# PreContV1.net
KiCad netlist of a schematic drawn in EAGLE
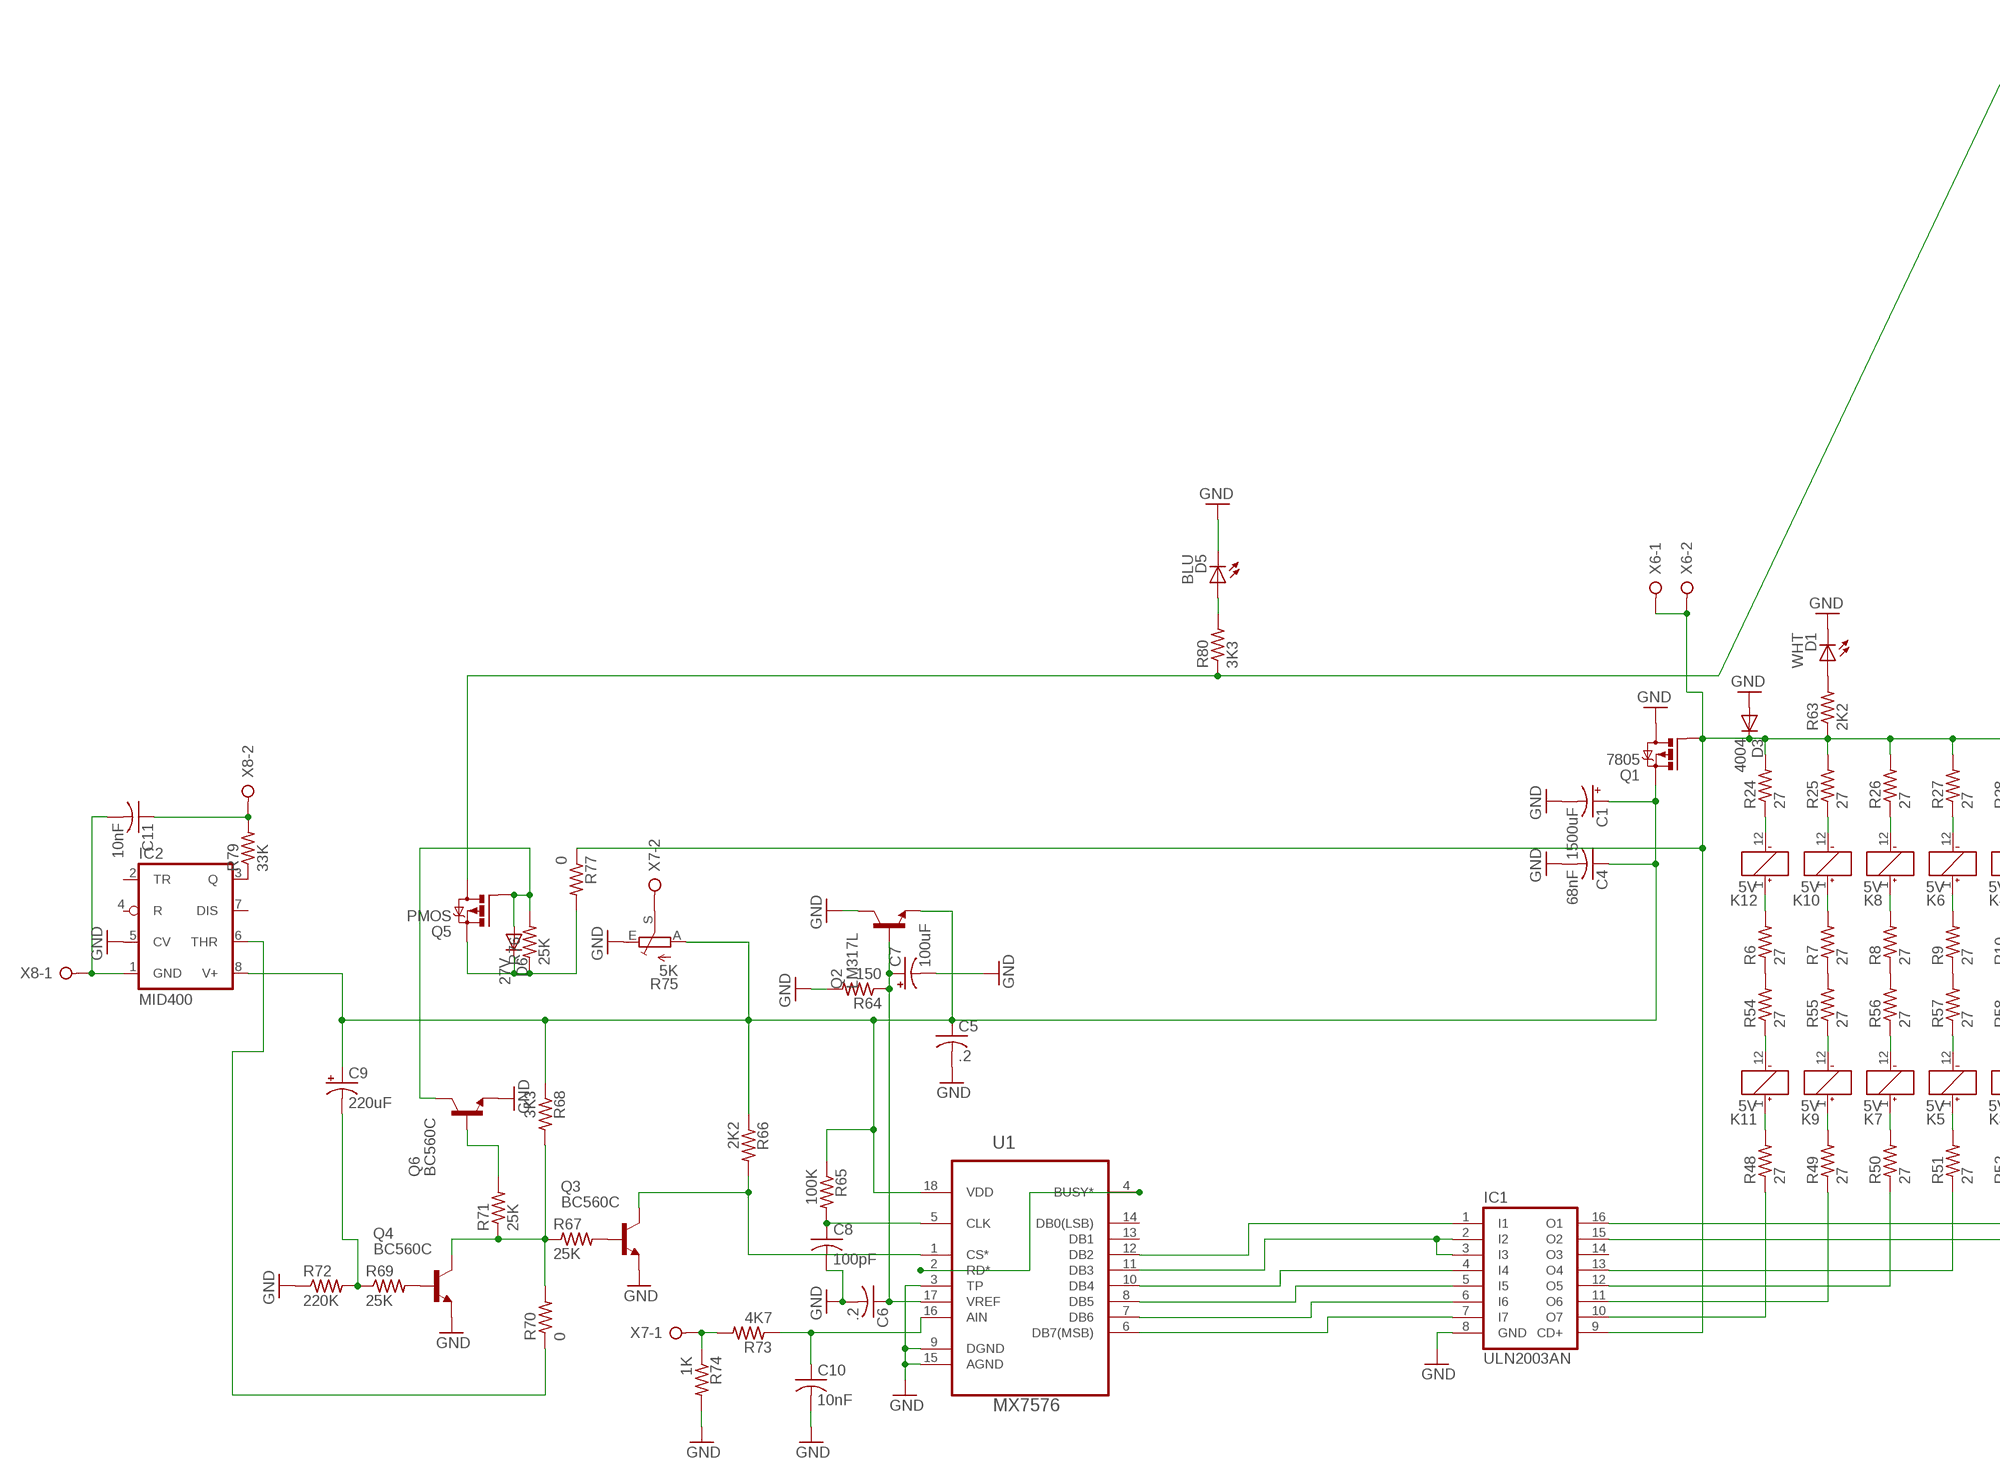
[diagram p0: schematic, sheet 1, part 1 of 2]
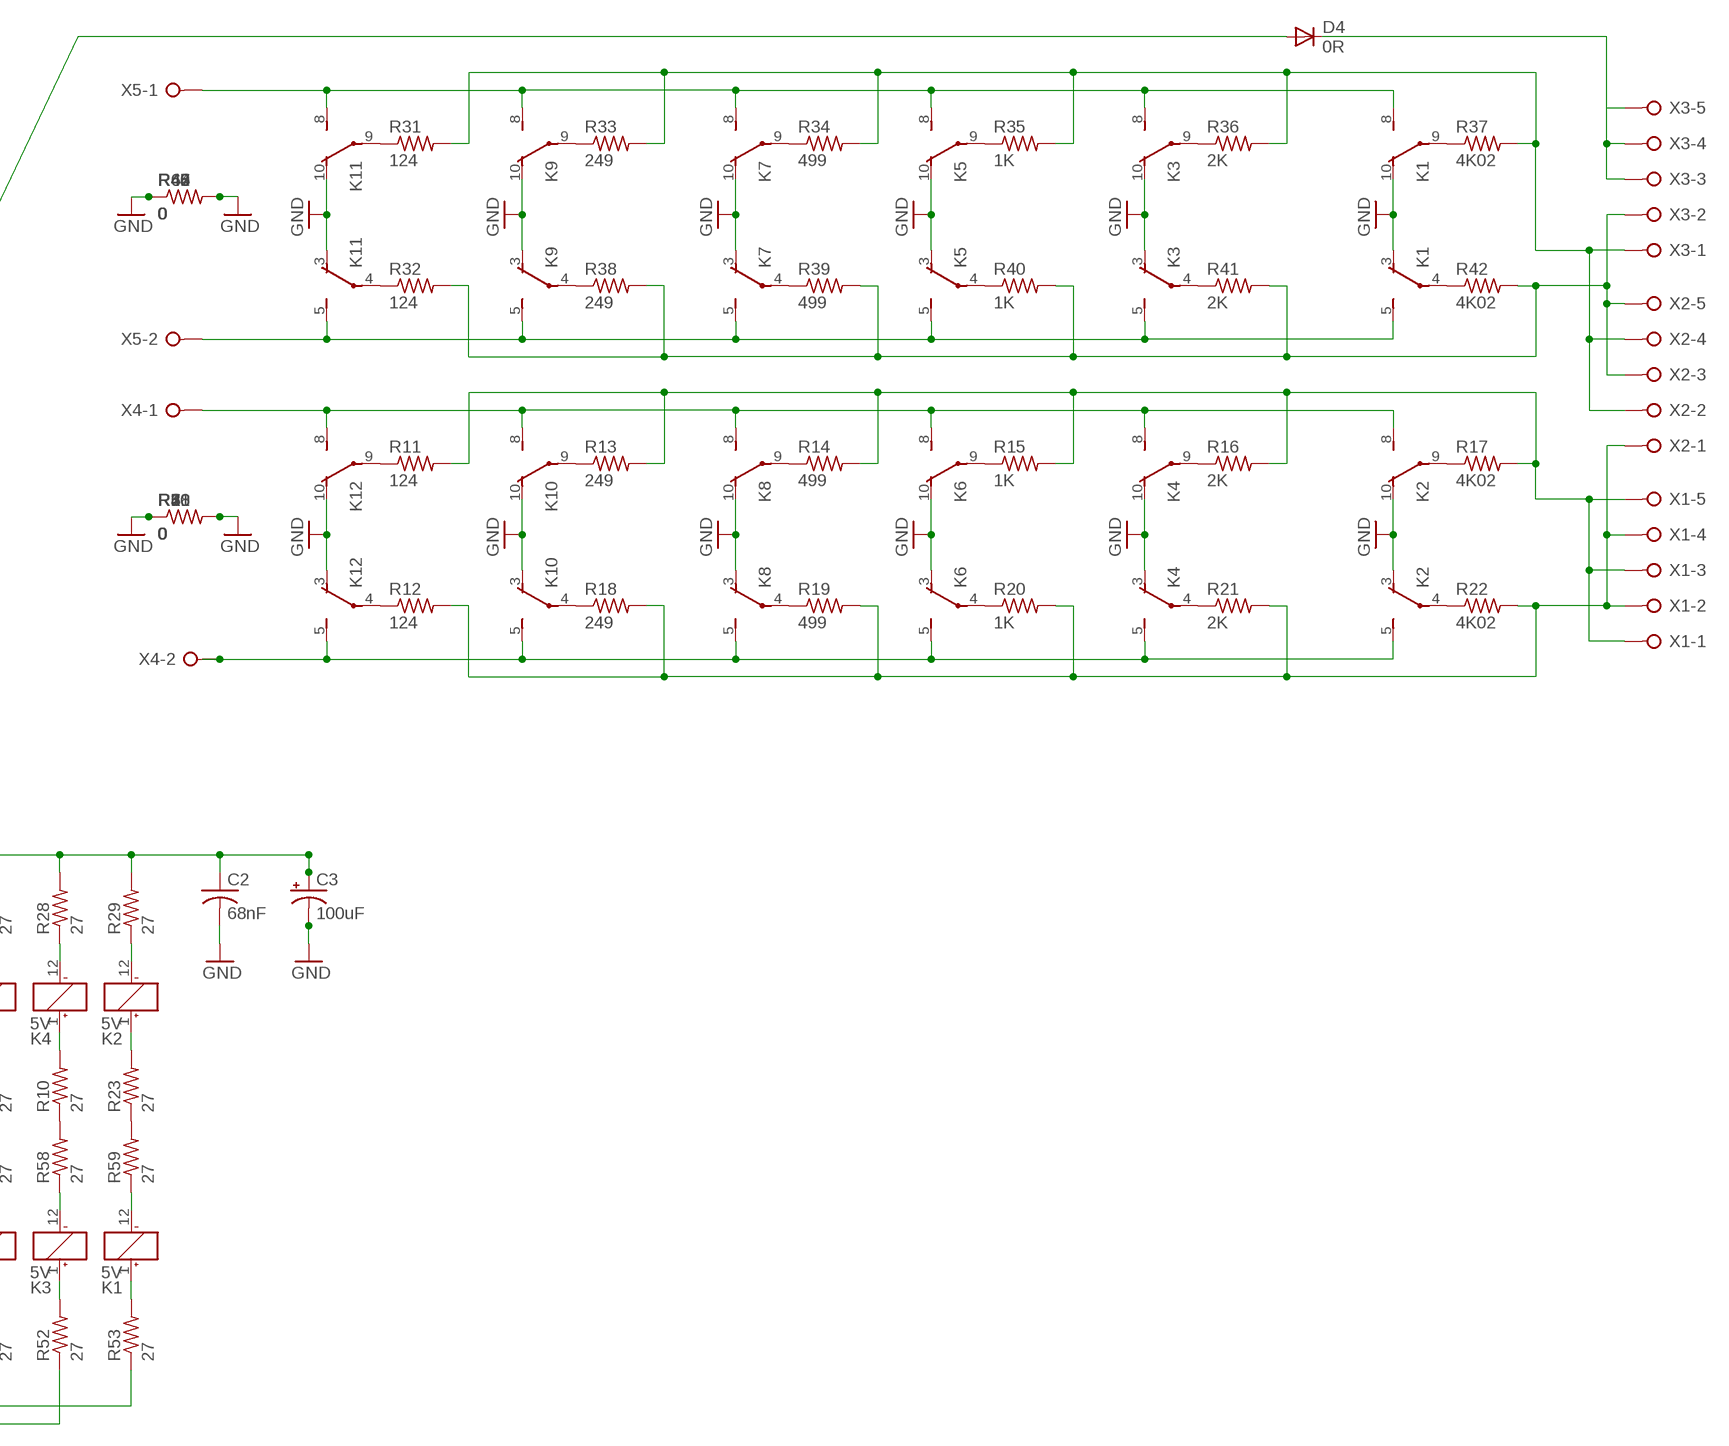
[diagram p1: schematic, sheet 1, part 2 of 2]

(export (version "E")
  (design (tool "Eeschema 10.0.6"))
  (components
    (comp (ref "C1")
      (value "1500uF")
      (footprint "eagle-import:E5-10,5")
      (libsource (lib "eagle-import") (part "CPOL-USE5-10.5"))
    )
    (comp (ref "C2")
      (value "68nF")
      (footprint "eagle-import:C075-042X103")
      (libsource (lib "eagle-import") (part "C-US075-042X103"))
    )
    (comp (ref "C3")
      (value "100uF")
      (footprint "eagle-import:E5-10,5")
      (libsource (lib "eagle-import") (part "CPOL-USE5-10.5"))
    )
    (comp (ref "C4")
      (value "68nF")
      (footprint "eagle-import:C075-042X103")
      (libsource (lib "eagle-import") (part "C-US075-042X103"))
    )
    (comp (ref "C5")
      (value ".2")
      (footprint "eagle-import:C1210K")
      (libsource (lib "eagle-import") (part "C-USC1210K"))
    )
    (comp (ref "C6")
      (value ".2")
      (footprint "eagle-import:C1210K")
      (libsource (lib "eagle-import") (part "C-USC1210K"))
    )
    (comp (ref "C7")
      (value "100uF")
      (footprint "eagle-import:E5-10,5")
      (libsource (lib "eagle-import") (part "CPOL-USE5-10.5"))
    )
    (comp (ref "C8")
      (value "100pF")
      (footprint "eagle-import:C050-075X075")
      (libsource (lib "eagle-import") (part "C-US050-075X075"))
    )
    (comp (ref "C9")
      (value "220uF")
      (footprint "eagle-import:E5-10,5")
      (libsource (lib "eagle-import") (part "CPOL-USE5-10.5"))
    )
    (comp (ref "C10")
      (value "10nF")
      (footprint "eagle-import:C050-075X075")
      (libsource (lib "eagle-import") (part "C-US050-075X075"))
    )
    (comp (ref "C11")
      (value "10nF")
      (footprint "eagle-import:C075-042X103")
      (libsource (lib "eagle-import") (part "C-US075-042X103"))
    )
    (comp (ref "D1")
      (value "WHT")
      (footprint "eagle-import:SFH482")
      (libsource (lib "eagle-import") (part "SFH482"))
    )
    (comp (ref "D3")
      (value "4004")
      (footprint "eagle-import:DO35-10")
      (libsource (lib "eagle-import") (part "1N4148DO35-10"))
    )
    (comp (ref "D4")
      (value "0R")
      (footprint "eagle-import:DO35-10")
      (libsource (lib "eagle-import") (part "1N4148DO35-10"))
    )
    (comp (ref "D5")
      (value "BLU")
      (footprint "eagle-import:SFH482")
      (libsource (lib "eagle-import") (part "SFH482"))
    )
    (comp (ref "D6")
      (value "27V")
      (footprint "eagle-import:DO35-7")
      (libsource (lib "eagle-import") (part "1N4148DO35-7"))
    )
    (comp (ref "IC1")
      (value "ULN2003AN")
      (footprint "eagle-import:DIL16")
      (libsource (lib "eagle-import") (part "ULN2003AN"))
    )
    (comp (ref "IC2")
      (value "MID400")
      (footprint "eagle-import:DIL08")
      (libsource (lib "eagle-import") (part "555NLM"))
    )
    (comp (ref "K1")
      (value "5V")
      (footprint "eagle-import:TX2")
      (fields
        (field (name "MF") "AROMAT/ MATSUSHITA")
        (field (name "MPN") "TX2-12V")
        (field (name "MF_1") "AROMAT/ MATSUSHITA")
        (field (name "MPN_1") "TX2-12V")
        (field (name "OC_FARNELL") "1200952")
        (field (name "OC_NEWARK") "67K1295")
      )
      (libsource (lib "eagle-import") (part "TX2?-12V"))
    )
    (comp (ref "K2")
      (value "5V")
      (footprint "eagle-import:TX2")
      (fields
        (field (name "MF") "AROMAT/ MATSUSHITA")
        (field (name "MPN") "TX2-12V")
        (field (name "MF_1") "AROMAT/ MATSUSHITA")
        (field (name "MPN_1") "TX2-12V")
        (field (name "OC_FARNELL") "1200952")
        (field (name "OC_NEWARK") "67K1295")
      )
      (libsource (lib "eagle-import") (part "TX2?-12V"))
    )
    (comp (ref "K3")
      (value "5V")
      (footprint "eagle-import:TX2")
      (fields
        (field (name "MF") "AROMAT/ MATSUSHITA")
        (field (name "MPN") "TX2-12V")
        (field (name "MF_1") "AROMAT/ MATSUSHITA")
        (field (name "MPN_1") "TX2-12V")
        (field (name "OC_FARNELL") "1200952")
        (field (name "OC_NEWARK") "67K1295")
      )
      (libsource (lib "eagle-import") (part "TX2?-12V"))
    )
    (comp (ref "K4")
      (value "5V")
      (footprint "eagle-import:TX2")
      (fields
        (field (name "MF") "AROMAT/ MATSUSHITA")
        (field (name "MPN") "TX2-12V")
        (field (name "MF_1") "AROMAT/ MATSUSHITA")
        (field (name "MPN_1") "TX2-12V")
        (field (name "OC_FARNELL") "1200952")
        (field (name "OC_NEWARK") "67K1295")
      )
      (libsource (lib "eagle-import") (part "TX2?-12V"))
    )
    (comp (ref "K5")
      (value "5V")
      (footprint "eagle-import:TX2")
      (fields
        (field (name "MF") "AROMAT/ MATSUSHITA")
        (field (name "MPN") "TX2-12V")
        (field (name "MF_1") "AROMAT/ MATSUSHITA")
        (field (name "MPN_1") "TX2-12V")
        (field (name "OC_FARNELL") "1200952")
        (field (name "OC_NEWARK") "67K1295")
      )
      (libsource (lib "eagle-import") (part "TX2?-12V"))
    )
    (comp (ref "K6")
      (value "5V")
      (footprint "eagle-import:TX2")
      (fields
        (field (name "MF") "AROMAT/ MATSUSHITA")
        (field (name "MPN") "TX2-12V")
        (field (name "MF_1") "AROMAT/ MATSUSHITA")
        (field (name "MPN_1") "TX2-12V")
        (field (name "OC_FARNELL") "1200952")
        (field (name "OC_NEWARK") "67K1295")
      )
      (libsource (lib "eagle-import") (part "TX2?-12V"))
    )
    (comp (ref "K7")
      (value "5V")
      (footprint "eagle-import:TX2")
      (fields
        (field (name "MF") "AROMAT/ MATSUSHITA")
        (field (name "MPN") "TX2-12V")
        (field (name "MF_1") "AROMAT/ MATSUSHITA")
        (field (name "MPN_1") "TX2-12V")
        (field (name "OC_FARNELL") "1200952")
        (field (name "OC_NEWARK") "67K1295")
      )
      (libsource (lib "eagle-import") (part "TX2?-12V"))
    )
    (comp (ref "K8")
      (value "5V")
      (footprint "eagle-import:TX2")
      (fields
        (field (name "MF") "AROMAT/ MATSUSHITA")
        (field (name "MPN") "TX2-12V")
        (field (name "MF_1") "AROMAT/ MATSUSHITA")
        (field (name "MPN_1") "TX2-12V")
        (field (name "OC_FARNELL") "1200952")
        (field (name "OC_NEWARK") "67K1295")
      )
      (libsource (lib "eagle-import") (part "TX2?-12V"))
    )
    (comp (ref "K9")
      (value "5V")
      (footprint "eagle-import:TX2")
      (fields
        (field (name "MF") "AROMAT/ MATSUSHITA")
        (field (name "MPN") "TX2-12V")
        (field (name "MF_1") "AROMAT/ MATSUSHITA")
        (field (name "MPN_1") "TX2-12V")
        (field (name "OC_FARNELL") "1200952")
        (field (name "OC_NEWARK") "67K1295")
      )
      (libsource (lib "eagle-import") (part "TX2?-12V"))
    )
    (comp (ref "K10")
      (value "5V")
      (footprint "eagle-import:TX2")
      (fields
        (field (name "MF") "AROMAT/ MATSUSHITA")
        (field (name "MPN") "TX2-12V")
        (field (name "MF_1") "AROMAT/ MATSUSHITA")
        (field (name "MPN_1") "TX2-12V")
        (field (name "OC_FARNELL") "1200952")
        (field (name "OC_NEWARK") "67K1295")
      )
      (libsource (lib "eagle-import") (part "TX2?-12V"))
    )
    (comp (ref "K11")
      (value "5V")
      (footprint "eagle-import:TX2")
      (fields
        (field (name "MF") "AROMAT/ MATSUSHITA")
        (field (name "MPN") "TX2-12V")
        (field (name "MF_1") "AROMAT/ MATSUSHITA")
        (field (name "MPN_1") "TX2-12V")
        (field (name "OC_FARNELL") "1200952")
        (field (name "OC_NEWARK") "67K1295")
      )
      (libsource (lib "eagle-import") (part "TX2?-12V"))
    )
    (comp (ref "K12")
      (value "5V")
      (footprint "eagle-import:TX2")
      (fields
        (field (name "MF") "AROMAT/ MATSUSHITA")
        (field (name "MPN") "TX2-12V")
        (field (name "MF_1") "AROMAT/ MATSUSHITA")
        (field (name "MPN_1") "TX2-12V")
        (field (name "OC_FARNELL") "1200952")
        (field (name "OC_NEWARK") "67K1295")
      )
      (libsource (lib "eagle-import") (part "TX2?-12V"))
    )
    (comp (ref "Q1")
      (value "7805")
      (footprint "eagle-import:TO220BH")
      (libsource (lib "eagle-import") (part "IRF4905"))
    )
    (comp (ref "Q2")
      (value "LM317L")
      (footprint "eagle-import:TO92-EBC")
      (libsource (lib "eagle-import") (part "BC550B"))
    )
    (comp (ref "Q3")
      (value "BC560C")
      (footprint "eagle-import:TO92-EBC")
      (libsource (lib "eagle-import") (part "BC550B"))
    )
    (comp (ref "Q4")
      (value "BC560C")
      (footprint "eagle-import:TO92-EBC")
      (libsource (lib "eagle-import") (part "BC550B"))
    )
    (comp (ref "Q5")
      (value "PMOS")
      (footprint "eagle-import:TO220BH")
      (libsource (lib "eagle-import") (part "IRF4905"))
    )
    (comp (ref "Q6")
      (value "BC560C")
      (footprint "eagle-import:TO92-EBC")
      (libsource (lib "eagle-import") (part "BC550B"))
    )
    (comp (ref "R1")
      (value "0")
      (footprint "eagle-import:0207_10")
      (libsource (lib "eagle-import") (part "R-US_0207/10"))
    )
    (comp (ref "R2")
      (value "0")
      (footprint "eagle-import:0207_10")
      (libsource (lib "eagle-import") (part "R-US_0207/10"))
    )
    (comp (ref "R3")
      (value "0")
      (footprint "eagle-import:0207_10")
      (libsource (lib "eagle-import") (part "R-US_0207/10"))
    )
    (comp (ref "R4")
      (value "0")
      (footprint "eagle-import:0207_10")
      (libsource (lib "eagle-import") (part "R-US_0207/10"))
    )
    (comp (ref "R5")
      (value "0")
      (footprint "eagle-import:0207_10")
      (libsource (lib "eagle-import") (part "R-US_0207/10"))
    )
    (comp (ref "R6")
      (value "27")
      (footprint "eagle-import:0207_10")
      (libsource (lib "eagle-import") (part "R-US_0207/10"))
    )
    (comp (ref "R7")
      (value "27")
      (footprint "eagle-import:0207_10")
      (libsource (lib "eagle-import") (part "R-US_0207/10"))
    )
    (comp (ref "R8")
      (value "27")
      (footprint "eagle-import:0207_10")
      (libsource (lib "eagle-import") (part "R-US_0207/10"))
    )
    (comp (ref "R9")
      (value "27")
      (footprint "eagle-import:0207_10")
      (libsource (lib "eagle-import") (part "R-US_0207/10"))
    )
    (comp (ref "R10")
      (value "27")
      (footprint "eagle-import:0207_10")
      (libsource (lib "eagle-import") (part "R-US_0207/10"))
    )
    (comp (ref "R11")
      (value "124")
      (footprint "eagle-import:0207_10")
      (libsource (lib "eagle-import") (part "R-US_0207/10"))
    )
    (comp (ref "R12")
      (value "124")
      (footprint "eagle-import:0207_10")
      (libsource (lib "eagle-import") (part "R-US_0207/10"))
    )
    (comp (ref "R13")
      (value "249")
      (footprint "eagle-import:0207_10")
      (libsource (lib "eagle-import") (part "R-US_0207/10"))
    )
    (comp (ref "R14")
      (value "499")
      (footprint "eagle-import:0207_10")
      (libsource (lib "eagle-import") (part "R-US_0207/10"))
    )
    (comp (ref "R15")
      (value "1K")
      (footprint "eagle-import:0207_10")
      (libsource (lib "eagle-import") (part "R-US_0207/10"))
    )
    (comp (ref "R16")
      (value "2K")
      (footprint "eagle-import:0207_10")
      (libsource (lib "eagle-import") (part "R-US_0207/10"))
    )
    (comp (ref "R17")
      (value "4K02")
      (footprint "eagle-import:0207_10")
      (libsource (lib "eagle-import") (part "R-US_0207/10"))
    )
    (comp (ref "R18")
      (value "249")
      (footprint "eagle-import:0207_10")
      (libsource (lib "eagle-import") (part "R-US_0207/10"))
    )
    (comp (ref "R19")
      (value "499")
      (footprint "eagle-import:0207_10")
      (libsource (lib "eagle-import") (part "R-US_0207/10"))
    )
    (comp (ref "R20")
      (value "1K")
      (footprint "eagle-import:0207_10")
      (libsource (lib "eagle-import") (part "R-US_0207/10"))
    )
    (comp (ref "R21")
      (value "2K")
      (footprint "eagle-import:0207_10")
      (libsource (lib "eagle-import") (part "R-US_0207/10"))
    )
    (comp (ref "R22")
      (value "4K02")
      (footprint "eagle-import:0207_10")
      (libsource (lib "eagle-import") (part "R-US_0207/10"))
    )
    (comp (ref "R23")
      (value "27")
      (footprint "eagle-import:0207_10")
      (libsource (lib "eagle-import") (part "R-US_0207/10"))
    )
    (comp (ref "R24")
      (value "27")
      (footprint "eagle-import:0207_10")
      (libsource (lib "eagle-import") (part "R-US_0207/10"))
    )
    (comp (ref "R25")
      (value "27")
      (footprint "eagle-import:0207_10")
      (libsource (lib "eagle-import") (part "R-US_0207/10"))
    )
    (comp (ref "R26")
      (value "27")
      (footprint "eagle-import:0207_10")
      (libsource (lib "eagle-import") (part "R-US_0207/10"))
    )
    (comp (ref "R27")
      (value "27")
      (footprint "eagle-import:0207_10")
      (libsource (lib "eagle-import") (part "R-US_0207/10"))
    )
    (comp (ref "R28")
      (value "27")
      (footprint "eagle-import:0207_10")
      (libsource (lib "eagle-import") (part "R-US_0207/10"))
    )
    (comp (ref "R29")
      (value "27")
      (footprint "eagle-import:0207_10")
      (libsource (lib "eagle-import") (part "R-US_0207/10"))
    )
    (comp (ref "R30")
      (value "0")
      (footprint "eagle-import:0207_10")
      (libsource (lib "eagle-import") (part "R-US_0207/10"))
    )
    (comp (ref "R31")
      (value "124")
      (footprint "eagle-import:0207_10")
      (libsource (lib "eagle-import") (part "R-US_0207/10"))
    )
    (comp (ref "R32")
      (value "124")
      (footprint "eagle-import:0207_10")
      (libsource (lib "eagle-import") (part "R-US_0207/10"))
    )
    (comp (ref "R33")
      (value "249")
      (footprint "eagle-import:0207_10")
      (libsource (lib "eagle-import") (part "R-US_0207/10"))
    )
    (comp (ref "R34")
      (value "499")
      (footprint "eagle-import:0207_10")
      (libsource (lib "eagle-import") (part "R-US_0207/10"))
    )
    (comp (ref "R35")
      (value "1K")
      (footprint "eagle-import:0207_10")
      (libsource (lib "eagle-import") (part "R-US_0207/10"))
    )
    (comp (ref "R36")
      (value "2K")
      (footprint "eagle-import:0207_10")
      (libsource (lib "eagle-import") (part "R-US_0207/10"))
    )
    (comp (ref "R37")
      (value "4K02")
      (footprint "eagle-import:0207_10")
      (libsource (lib "eagle-import") (part "R-US_0207/10"))
    )
    (comp (ref "R38")
      (value "249")
      (footprint "eagle-import:0207_10")
      (libsource (lib "eagle-import") (part "R-US_0207/10"))
    )
    (comp (ref "R39")
      (value "499")
      (footprint "eagle-import:0207_10")
      (libsource (lib "eagle-import") (part "R-US_0207/10"))
    )
    (comp (ref "R40")
      (value "1K")
      (footprint "eagle-import:0207_10")
      (libsource (lib "eagle-import") (part "R-US_0207/10"))
    )
    (comp (ref "R41")
      (value "2K")
      (footprint "eagle-import:0207_10")
      (libsource (lib "eagle-import") (part "R-US_0207/10"))
    )
    (comp (ref "R42")
      (value "4K02")
      (footprint "eagle-import:0207_10")
      (libsource (lib "eagle-import") (part "R-US_0207/10"))
    )
    (comp (ref "R43")
      (value "0")
      (footprint "eagle-import:0207_10")
      (libsource (lib "eagle-import") (part "R-US_0207/10"))
    )
    (comp (ref "R44")
      (value "0")
      (footprint "eagle-import:0207_10")
      (libsource (lib "eagle-import") (part "R-US_0207/10"))
    )
    (comp (ref "R45")
      (value "0")
      (footprint "eagle-import:0207_10")
      (libsource (lib "eagle-import") (part "R-US_0207/10"))
    )
    (comp (ref "R46")
      (value "0")
      (footprint "eagle-import:0207_10")
      (libsource (lib "eagle-import") (part "R-US_0207/10"))
    )
    (comp (ref "R47")
      (value "0")
      (footprint "eagle-import:0207_10")
      (libsource (lib "eagle-import") (part "R-US_0207/10"))
    )
    (comp (ref "R48")
      (value "27")
      (footprint "eagle-import:0207_10")
      (libsource (lib "eagle-import") (part "R-US_0207/10"))
    )
    (comp (ref "R49")
      (value "27")
      (footprint "eagle-import:0207_10")
      (libsource (lib "eagle-import") (part "R-US_0207/10"))
    )
    (comp (ref "R50")
      (value "27")
      (footprint "eagle-import:0207_10")
      (libsource (lib "eagle-import") (part "R-US_0207/10"))
    )
    (comp (ref "R51")
      (value "27")
      (footprint "eagle-import:0207_10")
      (libsource (lib "eagle-import") (part "R-US_0207/10"))
    )
    (comp (ref "R52")
      (value "27")
      (footprint "eagle-import:0207_10")
      (libsource (lib "eagle-import") (part "R-US_0207/10"))
    )
    (comp (ref "R53")
      (value "27")
      (footprint "eagle-import:0207_10")
      (libsource (lib "eagle-import") (part "R-US_0207/10"))
    )
    (comp (ref "R54")
      (value "27")
      (footprint "eagle-import:0207_12")
      (libsource (lib "eagle-import") (part "R-US_0207/12"))
    )
    (comp (ref "R55")
      (value "27")
      (footprint "eagle-import:0207_12")
      (libsource (lib "eagle-import") (part "R-US_0207/12"))
    )
    (comp (ref "R56")
      (value "27")
      (footprint "eagle-import:0207_12")
      (libsource (lib "eagle-import") (part "R-US_0207/12"))
    )
    (comp (ref "R57")
      (value "27")
      (footprint "eagle-import:0207_12")
      (libsource (lib "eagle-import") (part "R-US_0207/12"))
    )
    (comp (ref "R58")
      (value "27")
      (footprint "eagle-import:0207_12")
      (libsource (lib "eagle-import") (part "R-US_0207/12"))
    )
    (comp (ref "R59")
      (value "27")
      (footprint "eagle-import:0207_10")
      (libsource (lib "eagle-import") (part "R-US_0207/10"))
    )
    (comp (ref "R60")
      (value "0")
      (footprint "eagle-import:0207_10")
      (libsource (lib "eagle-import") (part "R-US_0207/10"))
    )
    (comp (ref "R61")
      (value "0")
      (footprint "eagle-import:0207_10")
      (libsource (lib "eagle-import") (part "R-US_0207/10"))
    )
    (comp (ref "R62")
      (value "0")
      (footprint "eagle-import:0207_10")
      (libsource (lib "eagle-import") (part "R-US_0207/10"))
    )
    (comp (ref "R63")
      (value "2K2")
      (footprint "eagle-import:0309_12")
      (libsource (lib "eagle-import") (part "R-US_0309/12"))
    )
    (comp (ref "R64")
      (value "150")
      (footprint "eagle-import:0207_10")
      (libsource (lib "eagle-import") (part "R-US_0207/10"))
    )
    (comp (ref "R65")
      (value "100K")
      (footprint "eagle-import:0207_10")
      (libsource (lib "eagle-import") (part "R-US_0207/10"))
    )
    (comp (ref "R66")
      (value "2K2")
      (footprint "eagle-import:0207_10")
      (libsource (lib "eagle-import") (part "R-US_0207/10"))
    )
    (comp (ref "R67")
      (value "25K")
      (footprint "eagle-import:0207_10")
      (libsource (lib "eagle-import") (part "R-US_0207/10"))
    )
    (comp (ref "R68")
      (value "3K3")
      (footprint "eagle-import:0207_10")
      (libsource (lib "eagle-import") (part "R-US_0207/10"))
    )
    (comp (ref "R69")
      (value "25K")
      (footprint "eagle-import:0207_10")
      (libsource (lib "eagle-import") (part "R-US_0207/10"))
    )
    (comp (ref "R70")
      (value "0")
      (footprint "eagle-import:0207_10")
      (libsource (lib "eagle-import") (part "R-US_0207/10"))
    )
    (comp (ref "R71")
      (value "25K")
      (footprint "eagle-import:0207_10")
      (libsource (lib "eagle-import") (part "R-US_0207/10"))
    )
    (comp (ref "R72")
      (value "220K")
      (footprint "eagle-import:0207_10")
      (libsource (lib "eagle-import") (part "R-US_0207/10"))
    )
    (comp (ref "R73")
      (value "4K7")
      (footprint "eagle-import:0207_10")
      (libsource (lib "eagle-import") (part "R-US_0207/10"))
    )
    (comp (ref "R74")
      (value "1K")
      (footprint "eagle-import:0207_10")
      (libsource (lib "eagle-import") (part "R-US_0207/10"))
    )
    (comp (ref "R75")
      (value "5K")
      (footprint "eagle-import:RJ9W")
      (libsource (lib "eagle-import") (part "TRIM_EU-RJ9W"))
    )
    (comp (ref "R76")
      (value "25K")
      (footprint "eagle-import:0207_10")
      (libsource (lib "eagle-import") (part "R-US_0207/10"))
    )
    (comp (ref "R77")
      (value "0")
      (footprint "eagle-import:0207_10")
      (libsource (lib "eagle-import") (part "R-US_0207/10"))
    )
    (comp (ref "R78")
      (value "0")
      (footprint "eagle-import:0207_10")
      (libsource (lib "eagle-import") (part "R-US_0207/10"))
    )
    (comp (ref "R79")
      (value "33K")
      (footprint "eagle-import:0309_12")
      (libsource (lib "eagle-import") (part "R-US_0309/12"))
    )
    (comp (ref "R80")
      (value "3K3")
      (footprint "eagle-import:0207_10")
      (libsource (lib "eagle-import") (part "R-US_0207/10"))
    )
    (comp (ref "U1")
      (value "MX7576")
      (footprint "eagle-import:DIP254P762X533-18P")
      (fields (field (name "MPN") "AD7575JNZ"))
      (libsource (lib "eagle-import") (part "AD7575JNZ"))
    )
    (comp (ref "X1")
      (value "W237-05P")
      (footprint "eagle-import:W237-5P")
      (libsource (lib "eagle-import") (part "W237-05P"))
    )
    (comp (ref "X2")
      (value "W237-05P")
      (footprint "eagle-import:W237-5P")
      (libsource (lib "eagle-import") (part "W237-05P"))
    )
    (comp (ref "X3")
      (value "W237-05P")
      (footprint "eagle-import:W237-5P")
      (fields (field (name "OC_FARNELL") "unknown") (field (name "OC_NEWARK") "unknown"))
      (libsource (lib "eagle-import") (part "W237-05P"))
    )
    (comp (ref "X4")
      (value "W237-02P")
      (footprint "eagle-import:W237-132")
      (libsource (lib "eagle-import") (part "W237-02P"))
    )
    (comp (ref "X5")
      (value "W237-02P")
      (footprint "eagle-import:W237-132")
      (libsource (lib "eagle-import") (part "W237-02P"))
    )
    (comp (ref "X6")
      (value "W237-02P")
      (footprint "eagle-import:W237-132")
      (fields (field (name "OC_FARNELL") "unknown") (field (name "OC_NEWARK") "unknown"))
      (libsource (lib "eagle-import") (part "W237-02P"))
    )
    (comp (ref "X7")
      (value "W237-02P")
      (footprint "eagle-import:W237-132")
      (fields (field (name "OC_FARNELL") "unknown") (field (name "OC_NEWARK") "unknown"))
      (libsource (lib "eagle-import") (part "W237-02P"))
    )
    (comp (ref "X8")
      (value "W237-02P")
      (footprint "eagle-import:W237-132")
      (fields (field (name "OC_FARNELL") "unknown") (field (name "OC_NEWARK") "unknown"))
      (libsource (lib "eagle-import") (part "W237-02P"))
    )
  )
  (nets
    (net (code "1") (name "GND") (class "Default")
      (node (ref "C1") (pin "-") (pinfunction "-_-") (pintype "passive"))
      (node (ref "C10") (pin "2") (pinfunction "2_2") (pintype "passive"))
      (node (ref "C2") (pin "2") (pinfunction "2_2") (pintype "passive"))
      (node (ref "C3") (pin "-") (pinfunction "-_-") (pintype "passive"))
      (node (ref "C4") (pin "2") (pinfunction "2_2") (pintype "passive"))
      (node (ref "C5") (pin "2") (pinfunction "2_2") (pintype "passive"))
      (node (ref "C6") (pin "2") (pinfunction "2_2") (pintype "passive"))
      (node (ref "C7") (pin "-") (pinfunction "-_-") (pintype "passive"))
      (node (ref "C8") (pin "2") (pinfunction "2_2") (pintype "passive"))
      (node (ref "D1") (pin "K") (pinfunction "C_K") (pintype "passive"))
      (node (ref "D3") (pin "A") (pinfunction "A_A") (pintype "passive"))
      (node (ref "D5") (pin "K") (pinfunction "C_K") (pintype "passive"))
      (node (ref "IC1") (pin "8") (pinfunction "GND_8") (pintype "power_in"))
      (node (ref "IC2") (pin "5") (pinfunction "CV_5") (pintype "input"))
      (node (ref "K1") (pin "10") (pinfunction "O_10") (pintype "passive"))
      (node (ref "K1") (pin "3") (pinfunction "O_3") (pintype "passive"))
      (node (ref "K10") (pin "10") (pinfunction "O_10") (pintype "passive"))
      (node (ref "K10") (pin "3") (pinfunction "O_3") (pintype "passive"))
      (node (ref "K11") (pin "10") (pinfunction "O_10") (pintype "passive"))
      (node (ref "K11") (pin "3") (pinfunction "O_3") (pintype "passive"))
      (node (ref "K12") (pin "10") (pinfunction "O_10") (pintype "passive"))
      (node (ref "K12") (pin "3") (pinfunction "O_3") (pintype "passive"))
      (node (ref "K2") (pin "10") (pinfunction "O_10") (pintype "passive"))
      (node (ref "K2") (pin "3") (pinfunction "O_3") (pintype "passive"))
      (node (ref "K3") (pin "10") (pinfunction "O_10") (pintype "passive"))
      (node (ref "K3") (pin "3") (pinfunction "O_3") (pintype "passive"))
      (node (ref "K4") (pin "10") (pinfunction "O_10") (pintype "passive"))
      (node (ref "K4") (pin "3") (pinfunction "O_3") (pintype "passive"))
      (node (ref "K5") (pin "10") (pinfunction "O_10") (pintype "passive"))
      (node (ref "K5") (pin "3") (pinfunction "O_3") (pintype "passive"))
      (node (ref "K6") (pin "10") (pinfunction "O_10") (pintype "passive"))
      (node (ref "K6") (pin "3") (pinfunction "O_3") (pintype "passive"))
      (node (ref "K7") (pin "10") (pinfunction "O_10") (pintype "passive"))
      (node (ref "K7") (pin "3") (pinfunction "O_3") (pintype "passive"))
      (node (ref "K8") (pin "10") (pinfunction "O_10") (pintype "passive"))
      (node (ref "K8") (pin "3") (pinfunction "O_3") (pintype "passive"))
      (node (ref "K9") (pin "10") (pinfunction "O_10") (pintype "passive"))
      (node (ref "K9") (pin "3") (pinfunction "O_3") (pintype "passive"))
      (node (ref "Q1") (pin "D") (pinfunction "D_D") (pintype "passive"))
      (node (ref "Q2") (pin "C") (pinfunction "C_C") (pintype "passive"))
      (node (ref "Q3") (pin "E") (pinfunction "E_E") (pintype "passive"))
      (node (ref "Q4") (pin "E") (pinfunction "E_E") (pintype "passive"))
      (node (ref "Q6") (pin "E") (pinfunction "E_E") (pintype "passive"))
      (node (ref "R1") (pin "1") (pinfunction "1_1") (pintype "passive"))
      (node (ref "R1") (pin "2") (pinfunction "2_2") (pintype "passive"))
      (node (ref "R2") (pin "1") (pinfunction "1_1") (pintype "passive"))
      (node (ref "R2") (pin "2") (pinfunction "2_2") (pintype "passive"))
      (node (ref "R3") (pin "1") (pinfunction "1_1") (pintype "passive"))
      (node (ref "R3") (pin "2") (pinfunction "2_2") (pintype "passive"))
      (node (ref "R30") (pin "1") (pinfunction "1_1") (pintype "passive"))
      (node (ref "R30") (pin "2") (pinfunction "2_2") (pintype "passive"))
      (node (ref "R4") (pin "1") (pinfunction "1_1") (pintype "passive"))
      (node (ref "R4") (pin "2") (pinfunction "2_2") (pintype "passive"))
      (node (ref "R43") (pin "1") (pinfunction "1_1") (pintype "passive"))
      (node (ref "R43") (pin "2") (pinfunction "2_2") (pintype "passive"))
      (node (ref "R44") (pin "1") (pinfunction "1_1") (pintype "passive"))
      (node (ref "R44") (pin "2") (pinfunction "2_2") (pintype "passive"))
      (node (ref "R45") (pin "1") (pinfunction "1_1") (pintype "passive"))
      (node (ref "R45") (pin "2") (pinfunction "2_2") (pintype "passive"))
      (node (ref "R46") (pin "1") (pinfunction "1_1") (pintype "passive"))
      (node (ref "R46") (pin "2") (pinfunction "2_2") (pintype "passive"))
      (node (ref "R47") (pin "1") (pinfunction "1_1") (pintype "passive"))
      (node (ref "R47") (pin "2") (pinfunction "2_2") (pintype "passive"))
      (node (ref "R5") (pin "1") (pinfunction "1_1") (pintype "passive"))
      (node (ref "R5") (pin "2") (pinfunction "2_2") (pintype "passive"))
      (node (ref "R60") (pin "1") (pinfunction "1_1") (pintype "passive"))
      (node (ref "R60") (pin "2") (pinfunction "2_2") (pintype "passive"))
      (node (ref "R61") (pin "1") (pinfunction "1_1") (pintype "passive"))
      (node (ref "R61") (pin "2") (pinfunction "2_2") (pintype "passive"))
      (node (ref "R62") (pin "1") (pinfunction "1_1") (pintype "passive"))
      (node (ref "R62") (pin "2") (pinfunction "2_2") (pintype "passive"))
      (node (ref "R64") (pin "2") (pinfunction "2_2") (pintype "passive"))
      (node (ref "R72") (pin "1") (pinfunction "1_1") (pintype "passive"))
      (node (ref "R74") (pin "2") (pinfunction "2_2") (pintype "passive"))
      (node (ref "R75") (pin "E") (pinfunction "E_E") (pintype "passive"))
      (node (ref "R78") (pin "1") (pinfunction "1_1") (pintype "passive"))
      (node (ref "R78") (pin "2") (pinfunction "2_2") (pintype "passive"))
      (node (ref "U1") (pin "15") (pinfunction "AGND_15") (pintype "passive"))
      (node (ref "U1") (pin "3") (pinfunction "TP_3") (pintype "input"))
      (node (ref "U1") (pin "9") (pinfunction "DGND_9") (pintype "passive"))
    )
    (net (code "2") (name "Net-(C9-Pad-)") (class "Default")
      (node (ref "C9") (pin "-") (pinfunction "-_-") (pintype "passive"))
      (node (ref "R69") (pin "1") (pinfunction "1_1") (pintype "passive"))
      (node (ref "R72") (pin "2") (pinfunction "2_2") (pintype "passive"))
    )
    (net (code "3") (name "Net-(D1-PadA)") (class "Default")
      (node (ref "D1") (pin "A") (pinfunction "A_A") (pintype "passive"))
      (node (ref "R63") (pin "2") (pinfunction "2_2") (pintype "passive"))
    )
    (net (code "4") (name "Net-(D4-PadA)") (class "Default")
      (node (ref "D4") (pin "A") (pinfunction "A_A") (pintype "passive"))
      (node (ref "Q5") (pin "D") (pinfunction "D_D") (pintype "passive"))
      (node (ref "R80") (pin "1") (pinfunction "1_1") (pintype "passive"))
    )
    (net (code "5") (name "Net-(D5-PadA)") (class "Default")
      (node (ref "D5") (pin "A") (pinfunction "A_A") (pintype "passive"))
      (node (ref "R80") (pin "2") (pinfunction "2_2") (pintype "passive"))
    )
    (net (code "6") (name "Net-(D6-PadA)") (class "Default")
      (node (ref "D6") (pin "A") (pinfunction "A_A") (pintype "passive"))
      (node (ref "Q5") (pin "G") (pinfunction "G_G") (pintype "passive"))
      (node (ref "Q6") (pin "C") (pinfunction "C_C") (pintype "passive"))
      (node (ref "R76") (pin "2") (pinfunction "2_2") (pintype "passive"))
    )
    (net (code "7") (name "Net-(D6-PadC)") (class "Default")
      (node (ref "D6") (pin "C") (pinfunction "C_C") (pintype "passive"))
      (node (ref "Q5") (pin "S") (pinfunction "S_S") (pintype "passive"))
      (node (ref "R76") (pin "1") (pinfunction "1_1") (pintype "passive"))
      (node (ref "R77") (pin "2") (pinfunction "2_2") (pintype "passive"))
    )
    (net (code "8") (name "Net-(IC1-CD+)") (class "Default")
      (node (ref "C2") (pin "1") (pinfunction "1_1") (pintype "passive"))
      (node (ref "C3") (pin "+") (pinfunction "+_+") (pintype "passive"))
      (node (ref "D3") (pin "C") (pinfunction "C_C") (pintype "passive"))
      (node (ref "IC1") (pin "9") (pinfunction "CD+_9") (pintype "passive"))
      (node (ref "Q1") (pin "G") (pinfunction "G_G") (pintype "passive"))
      (node (ref "R24") (pin "2") (pinfunction "2_2") (pintype "passive"))
      (node (ref "R25") (pin "2") (pinfunction "2_2") (pintype "passive"))
      (node (ref "R26") (pin "2") (pinfunction "2_2") (pintype "passive"))
      (node (ref "R27") (pin "2") (pinfunction "2_2") (pintype "passive"))
      (node (ref "R28") (pin "2") (pinfunction "2_2") (pintype "passive"))
      (node (ref "R29") (pin "2") (pinfunction "2_2") (pintype "passive"))
      (node (ref "R63") (pin "1") (pinfunction "1_1") (pintype "passive"))
      (node (ref "R77") (pin "1") (pinfunction "1_1") (pintype "passive"))
      (node (ref "X6") (pin "1") (pinfunction "KL_1") (pintype "passive"))
      (node (ref "X6") (pin "2") (pinfunction "KL_2") (pintype "passive"))
    )
    (net (code "9") (name "Net-(IC1-I1)") (class "Default")
      (node (ref "IC1") (pin "1") (pinfunction "I1_1") (pintype "input"))
      (node (ref "U1") (pin "12") (pinfunction "DB2_12") (pintype "output"))
    )
    (net (code "10") (name "Net-(IC1-I2)") (class "Default")
      (node (ref "IC1") (pin "2") (pinfunction "I2_2") (pintype "input"))
      (node (ref "IC1") (pin "3") (pinfunction "I3_3") (pintype "input"))
      (node (ref "U1") (pin "11") (pinfunction "DB3_11") (pintype "output"))
    )
    (net (code "11") (name "Net-(IC1-I4)") (class "Default")
      (node (ref "IC1") (pin "4") (pinfunction "I4_4") (pintype "input"))
      (node (ref "U1") (pin "10") (pinfunction "DB4_10") (pintype "output"))
    )
    (net (code "12") (name "Net-(IC1-I5)") (class "Default")
      (node (ref "IC1") (pin "5") (pinfunction "I5_5") (pintype "input"))
      (node (ref "U1") (pin "8") (pinfunction "DB5_8") (pintype "output"))
    )
    (net (code "13") (name "Net-(IC1-I6)") (class "Default")
      (node (ref "IC1") (pin "6") (pinfunction "I6_6") (pintype "input"))
      (node (ref "U1") (pin "7") (pinfunction "DB6_7") (pintype "output"))
    )
    (net (code "14") (name "Net-(IC1-I7)") (class "Default")
      (node (ref "IC1") (pin "7") (pinfunction "I7_7") (pintype "input"))
      (node (ref "U1") (pin "6") (pinfunction "DB7(MSB)_6") (pintype "output"))
    )
    (net (code "15") (name "Net-(IC1-O1)") (class "Default")
      (node (ref "IC1") (pin "16") (pinfunction "O1_16") (pintype "open_collector"))
      (node (ref "R53") (pin "1") (pinfunction "1_1") (pintype "passive"))
    )
    (net (code "16") (name "Net-(IC1-O2)") (class "Default")
      (node (ref "IC1") (pin "15") (pinfunction "O2_15") (pintype "open_collector"))
      (node (ref "R52") (pin "1") (pinfunction "1_1") (pintype "passive"))
    )
    (net (code "17") (name "Net-(IC1-O4)") (class "Default")
      (node (ref "IC1") (pin "13") (pinfunction "O4_13") (pintype "open_collector"))
      (node (ref "R51") (pin "1") (pinfunction "1_1") (pintype "passive"))
    )
    (net (code "18") (name "Net-(IC1-O5)") (class "Default")
      (node (ref "IC1") (pin "12") (pinfunction "O5_12") (pintype "open_collector"))
      (node (ref "R50") (pin "1") (pinfunction "1_1") (pintype "passive"))
    )
    (net (code "19") (name "Net-(IC1-O6)") (class "Default")
      (node (ref "IC1") (pin "11") (pinfunction "O6_11") (pintype "open_collector"))
      (node (ref "R49") (pin "1") (pinfunction "1_1") (pintype "passive"))
    )
    (net (code "20") (name "Net-(IC1-O7)") (class "Default")
      (node (ref "IC1") (pin "10") (pinfunction "O7_10") (pintype "open_collector"))
      (node (ref "R48") (pin "1") (pinfunction "1_1") (pintype "passive"))
    )
    (net (code "21") (name "Net-(IC2-GND)") (class "Default")
      (node (ref "C11") (pin "2") (pinfunction "2_2") (pintype "passive"))
      (node (ref "IC2") (pin "1") (pinfunction "GND_1") (pintype "power_in"))
      (node (ref "X8") (pin "1") (pinfunction "KL_1") (pintype "passive"))
    )
    (net (code "22") (name "Net-(IC2-Q)") (class "Default")
      (node (ref "IC2") (pin "3") (pinfunction "Q_3") (pintype "output"))
      (node (ref "R79") (pin "1") (pinfunction "1_1") (pintype "passive"))
    )
    (net (code "23") (name "Net-(IC2-THR)") (class "Default")
      (node (ref "IC2") (pin "6") (pinfunction "THR_6") (pintype "input"))
      (node (ref "R70") (pin "1") (pinfunction "1_1") (pintype "passive"))
    )
    (net (code "24") (name "Net-(IC2-V+)") (class "Default")
      (node (ref "C1") (pin "+") (pinfunction "+_+") (pintype "passive"))
      (node (ref "C4") (pin "1") (pinfunction "1_1") (pintype "passive"))
      (node (ref "C5") (pin "1") (pinfunction "1_1") (pintype "passive"))
      (node (ref "C9") (pin "+") (pinfunction "+_+") (pintype "passive"))
      (node (ref "IC2") (pin "8") (pinfunction "V+_8") (pintype "power_in"))
      (node (ref "Q1") (pin "S") (pinfunction "S_S") (pintype "passive"))
      (node (ref "Q2") (pin "E") (pinfunction "E_E") (pintype "passive"))
      (node (ref "R65") (pin "1") (pinfunction "1_1") (pintype "passive"))
      (node (ref "R66") (pin "1") (pinfunction "1_1") (pintype "passive"))
      (node (ref "R68") (pin "1") (pinfunction "1_1") (pintype "passive"))
      (node (ref "R75") (pin "A") (pinfunction "A_A") (pintype "passive"))
      (node (ref "U1") (pin "18") (pinfunction "VDD_18") (pintype "power_in"))
    )
    (net (code "25") (name "Net-(K1A-P)") (class "Default")
      (node (ref "K1") (pin "4") (pinfunction "P_4") (pintype "passive"))
      (node (ref "R42") (pin "1") (pinfunction "1_1") (pintype "passive"))
    )
    (net (code "26") (name "Net-(K1B-P)") (class "Default")
      (node (ref "K1") (pin "9") (pinfunction "P_9") (pintype "passive"))
      (node (ref "R37") (pin "1") (pinfunction "1_1") (pintype "passive"))
    )
    (net (code "27") (name "Net-(K1C-+)") (class "Default")
      (node (ref "K1") (pin "1") (pinfunction "+_1") (pintype "passive"))
      (node (ref "R53") (pin "2") (pinfunction "2_2") (pintype "passive"))
    )
    (net (code "28") (name "Net-(K1C--)") (class "Default")
      (node (ref "K1") (pin "12") (pinfunction "-_12") (pintype "passive"))
      (node (ref "R59") (pin "1") (pinfunction "1_1") (pintype "passive"))
    )
    (net (code "29") (name "Net-(K2A-P)") (class "Default")
      (node (ref "K2") (pin "4") (pinfunction "P_4") (pintype "passive"))
      (node (ref "R22") (pin "1") (pinfunction "1_1") (pintype "passive"))
    )
    (net (code "30") (name "Net-(K2B-P)") (class "Default")
      (node (ref "K2") (pin "9") (pinfunction "P_9") (pintype "passive"))
      (node (ref "R17") (pin "1") (pinfunction "1_1") (pintype "passive"))
    )
    (net (code "31") (name "Net-(K2C-+)") (class "Default")
      (node (ref "K2") (pin "1") (pinfunction "+_1") (pintype "passive"))
      (node (ref "R23") (pin "2") (pinfunction "2_2") (pintype "passive"))
    )
    (net (code "32") (name "Net-(K2C--)") (class "Default")
      (node (ref "K2") (pin "12") (pinfunction "-_12") (pintype "passive"))
      (node (ref "R29") (pin "1") (pinfunction "1_1") (pintype "passive"))
    )
    (net (code "33") (name "Net-(K3A-P)") (class "Default")
      (node (ref "K3") (pin "4") (pinfunction "P_4") (pintype "passive"))
      (node (ref "R41") (pin "1") (pinfunction "1_1") (pintype "passive"))
    )
    (net (code "34") (name "Net-(K3B-P)") (class "Default")
      (node (ref "K3") (pin "9") (pinfunction "P_9") (pintype "passive"))
      (node (ref "R36") (pin "1") (pinfunction "1_1") (pintype "passive"))
    )
    (net (code "35") (name "Net-(K3C-+)") (class "Default")
      (node (ref "K3") (pin "1") (pinfunction "+_1") (pintype "passive"))
      (node (ref "R52") (pin "2") (pinfunction "2_2") (pintype "passive"))
    )
    (net (code "36") (name "Net-(K3C--)") (class "Default")
      (node (ref "K3") (pin "12") (pinfunction "-_12") (pintype "passive"))
      (node (ref "R58") (pin "1") (pinfunction "1_1") (pintype "passive"))
    )
    (net (code "37") (name "Net-(K4A-P)") (class "Default")
      (node (ref "K4") (pin "4") (pinfunction "P_4") (pintype "passive"))
      (node (ref "R21") (pin "1") (pinfunction "1_1") (pintype "passive"))
    )
    (net (code "38") (name "Net-(K4B-P)") (class "Default")
      (node (ref "K4") (pin "9") (pinfunction "P_9") (pintype "passive"))
      (node (ref "R16") (pin "1") (pinfunction "1_1") (pintype "passive"))
    )
    (net (code "39") (name "Net-(K4C-+)") (class "Default")
      (node (ref "K4") (pin "1") (pinfunction "+_1") (pintype "passive"))
      (node (ref "R10") (pin "2") (pinfunction "2_2") (pintype "passive"))
    )
    (net (code "40") (name "Net-(K4C--)") (class "Default")
      (node (ref "K4") (pin "12") (pinfunction "-_12") (pintype "passive"))
      (node (ref "R28") (pin "1") (pinfunction "1_1") (pintype "passive"))
    )
    (net (code "41") (name "Net-(K5A-P)") (class "Default")
      (node (ref "K5") (pin "4") (pinfunction "P_4") (pintype "passive"))
      (node (ref "R40") (pin "1") (pinfunction "1_1") (pintype "passive"))
    )
    (net (code "42") (name "Net-(K5B-P)") (class "Default")
      (node (ref "K5") (pin "9") (pinfunction "P_9") (pintype "passive"))
      (node (ref "R35") (pin "1") (pinfunction "1_1") (pintype "passive"))
    )
    (net (code "43") (name "Net-(K5C-+)") (class "Default")
      (node (ref "K5") (pin "1") (pinfunction "+_1") (pintype "passive"))
      (node (ref "R51") (pin "2") (pinfunction "2_2") (pintype "passive"))
    )
    (net (code "44") (name "Net-(K5C--)") (class "Default")
      (node (ref "K5") (pin "12") (pinfunction "-_12") (pintype "passive"))
      (node (ref "R57") (pin "1") (pinfunction "1_1") (pintype "passive"))
    )
    (net (code "45") (name "Net-(K6A-P)") (class "Default")
      (node (ref "K6") (pin "4") (pinfunction "P_4") (pintype "passive"))
      (node (ref "R20") (pin "1") (pinfunction "1_1") (pintype "passive"))
    )
    (net (code "46") (name "Net-(K6B-P)") (class "Default")
      (node (ref "K6") (pin "9") (pinfunction "P_9") (pintype "passive"))
      (node (ref "R15") (pin "1") (pinfunction "1_1") (pintype "passive"))
    )
    (net (code "47") (name "Net-(K6C-+)") (class "Default")
      (node (ref "K6") (pin "1") (pinfunction "+_1") (pintype "passive"))
      (node (ref "R9") (pin "2") (pinfunction "2_2") (pintype "passive"))
    )
    (net (code "48") (name "Net-(K6C--)") (class "Default")
      (node (ref "K6") (pin "12") (pinfunction "-_12") (pintype "passive"))
      (node (ref "R27") (pin "1") (pinfunction "1_1") (pintype "passive"))
    )
    (net (code "49") (name "Net-(K7A-P)") (class "Default")
      (node (ref "K7") (pin "4") (pinfunction "P_4") (pintype "passive"))
      (node (ref "R39") (pin "1") (pinfunction "1_1") (pintype "passive"))
    )
    (net (code "50") (name "Net-(K7B-P)") (class "Default")
      (node (ref "K7") (pin "9") (pinfunction "P_9") (pintype "passive"))
      (node (ref "R34") (pin "1") (pinfunction "1_1") (pintype "passive"))
    )
    (net (code "51") (name "Net-(K7C-+)") (class "Default")
      (node (ref "K7") (pin "1") (pinfunction "+_1") (pintype "passive"))
      (node (ref "R50") (pin "2") (pinfunction "2_2") (pintype "passive"))
    )
    (net (code "52") (name "Net-(K7C--)") (class "Default")
      (node (ref "K7") (pin "12") (pinfunction "-_12") (pintype "passive"))
      (node (ref "R56") (pin "1") (pinfunction "1_1") (pintype "passive"))
    )
    (net (code "53") (name "Net-(K8A-P)") (class "Default")
      (node (ref "K8") (pin "4") (pinfunction "P_4") (pintype "passive"))
      (node (ref "R19") (pin "1") (pinfunction "1_1") (pintype "passive"))
    )
    (net (code "54") (name "Net-(K8B-P)") (class "Default")
      (node (ref "K8") (pin "9") (pinfunction "P_9") (pintype "passive"))
      (node (ref "R14") (pin "1") (pinfunction "1_1") (pintype "passive"))
    )
    (net (code "55") (name "Net-(K8C-+)") (class "Default")
      (node (ref "K8") (pin "1") (pinfunction "+_1") (pintype "passive"))
      (node (ref "R8") (pin "2") (pinfunction "2_2") (pintype "passive"))
    )
    (net (code "56") (name "Net-(K8C--)") (class "Default")
      (node (ref "K8") (pin "12") (pinfunction "-_12") (pintype "passive"))
      (node (ref "R26") (pin "1") (pinfunction "1_1") (pintype "passive"))
    )
    (net (code "57") (name "Net-(K9A-P)") (class "Default")
      (node (ref "K9") (pin "4") (pinfunction "P_4") (pintype "passive"))
      (node (ref "R38") (pin "1") (pinfunction "1_1") (pintype "passive"))
    )
    (net (code "58") (name "Net-(K9B-P)") (class "Default")
      (node (ref "K9") (pin "9") (pinfunction "P_9") (pintype "passive"))
      (node (ref "R33") (pin "1") (pinfunction "1_1") (pintype "passive"))
    )
    (net (code "59") (name "Net-(K9C-+)") (class "Default")
      (node (ref "K9") (pin "1") (pinfunction "+_1") (pintype "passive"))
      (node (ref "R49") (pin "2") (pinfunction "2_2") (pintype "passive"))
    )
    (net (code "60") (name "Net-(K9C--)") (class "Default")
      (node (ref "K9") (pin "12") (pinfunction "-_12") (pintype "passive"))
      (node (ref "R55") (pin "1") (pinfunction "1_1") (pintype "passive"))
    )
    (net (code "61") (name "Net-(K10A-P)") (class "Default")
      (node (ref "K10") (pin "4") (pinfunction "P_4") (pintype "passive"))
      (node (ref "R18") (pin "1") (pinfunction "1_1") (pintype "passive"))
    )
    (net (code "62") (name "Net-(K10A-S)") (class "Default")
      (node (ref "K10") (pin "5") (pinfunction "S_5") (pintype "passive"))
      (node (ref "K12") (pin "5") (pinfunction "S_5") (pintype "passive"))
      (node (ref "K2") (pin "5") (pinfunction "S_5") (pintype "passive"))
      (node (ref "K4") (pin "5") (pinfunction "S_5") (pintype "passive"))
      (node (ref "K6") (pin "5") (pinfunction "S_5") (pintype "passive"))
      (node (ref "K8") (pin "5") (pinfunction "S_5") (pintype "passive"))
      (node (ref "X4") (pin "2") (pinfunction "KL_2") (pintype "passive"))
    )
    (net (code "63") (name "Net-(K10B-P)") (class "Default")
      (node (ref "K10") (pin "9") (pinfunction "P_9") (pintype "passive"))
      (node (ref "R13") (pin "1") (pinfunction "1_1") (pintype "passive"))
    )
    (net (code "64") (name "Net-(K10B-S)") (class "Default")
      (node (ref "K10") (pin "8") (pinfunction "S_8") (pintype "passive"))
      (node (ref "K12") (pin "8") (pinfunction "S_8") (pintype "passive"))
      (node (ref "K2") (pin "8") (pinfunction "S_8") (pintype "passive"))
      (node (ref "K4") (pin "8") (pinfunction "S_8") (pintype "passive"))
      (node (ref "K6") (pin "8") (pinfunction "S_8") (pintype "passive"))
      (node (ref "K8") (pin "8") (pinfunction "S_8") (pintype "passive"))
      (node (ref "X4") (pin "1") (pinfunction "KL_1") (pintype "passive"))
    )
    (net (code "65") (name "Net-(K10C-+)") (class "Default")
      (node (ref "K10") (pin "1") (pinfunction "+_1") (pintype "passive"))
      (node (ref "R7") (pin "2") (pinfunction "2_2") (pintype "passive"))
    )
    (net (code "66") (name "Net-(K10C--)") (class "Default")
      (node (ref "K10") (pin "12") (pinfunction "-_12") (pintype "passive"))
      (node (ref "R25") (pin "1") (pinfunction "1_1") (pintype "passive"))
    )
    (net (code "67") (name "Net-(K11A-P)") (class "Default")
      (node (ref "K11") (pin "4") (pinfunction "P_4") (pintype "passive"))
      (node (ref "R32") (pin "1") (pinfunction "1_1") (pintype "passive"))
    )
    (net (code "68") (name "Net-(K11A-S)") (class "Default")
      (node (ref "K1") (pin "5") (pinfunction "S_5") (pintype "passive"))
      (node (ref "K11") (pin "5") (pinfunction "S_5") (pintype "passive"))
      (node (ref "K3") (pin "5") (pinfunction "S_5") (pintype "passive"))
      (node (ref "K5") (pin "5") (pinfunction "S_5") (pintype "passive"))
      (node (ref "K7") (pin "5") (pinfunction "S_5") (pintype "passive"))
      (node (ref "K9") (pin "5") (pinfunction "S_5") (pintype "passive"))
      (node (ref "X5") (pin "2") (pinfunction "KL_2") (pintype "passive"))
    )
    (net (code "69") (name "Net-(K11B-P)") (class "Default")
      (node (ref "K11") (pin "9") (pinfunction "P_9") (pintype "passive"))
      (node (ref "R31") (pin "1") (pinfunction "1_1") (pintype "passive"))
    )
    (net (code "70") (name "Net-(K11B-S)") (class "Default")
      (node (ref "K1") (pin "8") (pinfunction "S_8") (pintype "passive"))
      (node (ref "K11") (pin "8") (pinfunction "S_8") (pintype "passive"))
      (node (ref "K3") (pin "8") (pinfunction "S_8") (pintype "passive"))
      (node (ref "K5") (pin "8") (pinfunction "S_8") (pintype "passive"))
      (node (ref "K7") (pin "8") (pinfunction "S_8") (pintype "passive"))
      (node (ref "K9") (pin "8") (pinfunction "S_8") (pintype "passive"))
      (node (ref "X5") (pin "1") (pinfunction "KL_1") (pintype "passive"))
    )
    (net (code "71") (name "Net-(K11C-+)") (class "Default")
      (node (ref "K11") (pin "1") (pinfunction "+_1") (pintype "passive"))
      (node (ref "R48") (pin "2") (pinfunction "2_2") (pintype "passive"))
    )
    (net (code "72") (name "Net-(K11C--)") (class "Default")
      (node (ref "K11") (pin "12") (pinfunction "-_12") (pintype "passive"))
      (node (ref "R54") (pin "1") (pinfunction "1_1") (pintype "passive"))
    )
    (net (code "73") (name "Net-(K12A-P)") (class "Default")
      (node (ref "K12") (pin "4") (pinfunction "P_4") (pintype "passive"))
      (node (ref "R12") (pin "1") (pinfunction "1_1") (pintype "passive"))
    )
    (net (code "74") (name "Net-(K12B-P)") (class "Default")
      (node (ref "K12") (pin "9") (pinfunction "P_9") (pintype "passive"))
      (node (ref "R11") (pin "1") (pinfunction "1_1") (pintype "passive"))
    )
    (net (code "75") (name "Net-(K12C-+)") (class "Default")
      (node (ref "K12") (pin "1") (pinfunction "+_1") (pintype "passive"))
      (node (ref "R6") (pin "2") (pinfunction "2_2") (pintype "passive"))
    )
    (net (code "76") (name "Net-(K12C--)") (class "Default")
      (node (ref "K12") (pin "12") (pinfunction "-_12") (pintype "passive"))
      (node (ref "R24") (pin "1") (pinfunction "1_1") (pintype "passive"))
    )
    (net (code "77") (name "Net-(Q3-PadB)") (class "Default")
      (node (ref "Q3") (pin "B") (pinfunction "B_B") (pintype "passive"))
      (node (ref "R67") (pin "2") (pinfunction "2_2") (pintype "passive"))
    )
    (net (code "78") (name "Net-(Q4-PadB)") (class "Default")
      (node (ref "Q4") (pin "B") (pinfunction "B_B") (pintype "passive"))
      (node (ref "R69") (pin "2") (pinfunction "2_2") (pintype "passive"))
    )
    (net (code "79") (name "Net-(Q4-PadC)") (class "Default")
      (node (ref "Q4") (pin "C") (pinfunction "C_C") (pintype "passive"))
      (node (ref "R67") (pin "1") (pinfunction "1_1") (pintype "passive"))
      (node (ref "R68") (pin "2") (pinfunction "2_2") (pintype "passive"))
      (node (ref "R70") (pin "2") (pinfunction "2_2") (pintype "passive"))
      (node (ref "R71") (pin "1") (pinfunction "1_1") (pintype "passive"))
    )
    (net (code "80") (name "Net-(Q6-PadB)") (class "Default")
      (node (ref "Q6") (pin "B") (pinfunction "B_B") (pintype "passive"))
      (node (ref "R71") (pin "2") (pinfunction "2_2") (pintype "passive"))
    )
    (net (code "81") (name "Net-(R10-Pad1)") (class "Default")
      (node (ref "R10") (pin "1") (pinfunction "1_1") (pintype "passive"))
      (node (ref "R58") (pin "2") (pinfunction "2_2") (pintype "passive"))
    )
    (net (code "82") (name "Net-(R23-Pad1)") (class "Default")
      (node (ref "R23") (pin "1") (pinfunction "1_1") (pintype "passive"))
      (node (ref "R59") (pin "2") (pinfunction "2_2") (pintype "passive"))
    )
    (net (code "83") (name "Net-(R54-Pad2)") (class "Default")
      (node (ref "R54") (pin "2") (pinfunction "2_2") (pintype "passive"))
      (node (ref "R6") (pin "1") (pinfunction "1_1") (pintype "passive"))
    )
    (net (code "84") (name "Net-(R55-Pad2)") (class "Default")
      (node (ref "R55") (pin "2") (pinfunction "2_2") (pintype "passive"))
      (node (ref "R7") (pin "1") (pinfunction "1_1") (pintype "passive"))
    )
    (net (code "85") (name "Net-(R56-Pad2)") (class "Default")
      (node (ref "R56") (pin "2") (pinfunction "2_2") (pintype "passive"))
      (node (ref "R8") (pin "1") (pinfunction "1_1") (pintype "passive"))
    )
    (net (code "86") (name "Net-(R57-Pad2)") (class "Default")
      (node (ref "R57") (pin "2") (pinfunction "2_2") (pintype "passive"))
      (node (ref "R9") (pin "1") (pinfunction "1_1") (pintype "passive"))
    )
    (net (code "87") (name "Net-(U1-AIN)") (class "Default")
      (node (ref "C10") (pin "1") (pinfunction "1_1") (pintype "passive"))
      (node (ref "R73") (pin "1") (pinfunction "1_1") (pintype "passive"))
      (node (ref "U1") (pin "16") (pinfunction "AIN_16") (pintype "input"))
    )
    (net (code "88") (name "Net-(U1-BUSY*)") (class "Default")
      (node (ref "U1") (pin "2") (pinfunction "RD*_2") (pintype "input"))
      (node (ref "U1") (pin "4") (pinfunction "BUSY*_4") (pintype "passive"))
    )
    (net (code "89") (name "Net-(U1-CLK)") (class "Default")
      (node (ref "C8") (pin "1") (pinfunction "1_1") (pintype "passive"))
      (node (ref "R65") (pin "2") (pinfunction "2_2") (pintype "passive"))
      (node (ref "U1") (pin "5") (pinfunction "CLK_5") (pintype "input"))
    )
    (net (code "90") (name "Net-(U1-CS*)") (class "Default")
      (node (ref "Q3") (pin "C") (pinfunction "C_C") (pintype "passive"))
      (node (ref "R66") (pin "2") (pinfunction "2_2") (pintype "passive"))
      (node (ref "U1") (pin "1") (pinfunction "CS*_1") (pintype "input"))
    )
    (net (code "91") (name "Net-(U1-VREF)") (class "Default")
      (node (ref "C6") (pin "1") (pinfunction "1_1") (pintype "passive"))
      (node (ref "C7") (pin "+") (pinfunction "+_+") (pintype "passive"))
      (node (ref "Q2") (pin "B") (pinfunction "B_B") (pintype "passive"))
      (node (ref "R64") (pin "1") (pinfunction "1_1") (pintype "passive"))
      (node (ref "U1") (pin "17") (pinfunction "VREF_17") (pintype "input"))
    )
    (net (code "92") (name "Net-(X1A-KL)") (class "Default")
      (node (ref "R11") (pin "2") (pinfunction "2_2") (pintype "passive"))
      (node (ref "R13") (pin "2") (pinfunction "2_2") (pintype "passive"))
      (node (ref "R14") (pin "2") (pinfunction "2_2") (pintype "passive"))
      (node (ref "R15") (pin "2") (pinfunction "2_2") (pintype "passive"))
      (node (ref "R16") (pin "2") (pinfunction "2_2") (pintype "passive"))
      (node (ref "R17") (pin "2") (pinfunction "2_2") (pintype "passive"))
      (node (ref "X1") (pin "1") (pinfunction "KL_1") (pintype "passive"))
      (node (ref "X1") (pin "3") (pinfunction "KL_3") (pintype "passive"))
      (node (ref "X1") (pin "5") (pinfunction "KL_5") (pintype "passive"))
    )
    (net (code "93") (name "Net-(X1B-KL)") (class "Default")
      (node (ref "R12") (pin "2") (pinfunction "2_2") (pintype "passive"))
      (node (ref "R18") (pin "2") (pinfunction "2_2") (pintype "passive"))
      (node (ref "R19") (pin "2") (pinfunction "2_2") (pintype "passive"))
      (node (ref "R20") (pin "2") (pinfunction "2_2") (pintype "passive"))
      (node (ref "R21") (pin "2") (pinfunction "2_2") (pintype "passive"))
      (node (ref "R22") (pin "2") (pinfunction "2_2") (pintype "passive"))
      (node (ref "X1") (pin "2") (pinfunction "KL_2") (pintype "passive"))
      (node (ref "X1") (pin "4") (pinfunction "KL_4") (pintype "passive"))
      (node (ref "X2") (pin "1") (pinfunction "KL_1") (pintype "passive"))
    )
    (net (code "94") (name "Net-(X2B-KL)") (class "Default")
      (node (ref "R31") (pin "2") (pinfunction "2_2") (pintype "passive"))
      (node (ref "R33") (pin "2") (pinfunction "2_2") (pintype "passive"))
      (node (ref "R34") (pin "2") (pinfunction "2_2") (pintype "passive"))
      (node (ref "R35") (pin "2") (pinfunction "2_2") (pintype "passive"))
      (node (ref "R36") (pin "2") (pinfunction "2_2") (pintype "passive"))
      (node (ref "R37") (pin "2") (pinfunction "2_2") (pintype "passive"))
      (node (ref "X2") (pin "2") (pinfunction "KL_2") (pintype "passive"))
      (node (ref "X2") (pin "4") (pinfunction "KL_4") (pintype "passive"))
      (node (ref "X3") (pin "1") (pinfunction "KL_1") (pintype "passive"))
    )
    (net (code "95") (name "Net-(X2C-KL)") (class "Default")
      (node (ref "R32") (pin "2") (pinfunction "2_2") (pintype "passive"))
      (node (ref "R38") (pin "2") (pinfunction "2_2") (pintype "passive"))
      (node (ref "R39") (pin "2") (pinfunction "2_2") (pintype "passive"))
      (node (ref "R40") (pin "2") (pinfunction "2_2") (pintype "passive"))
      (node (ref "R41") (pin "2") (pinfunction "2_2") (pintype "passive"))
      (node (ref "R42") (pin "2") (pinfunction "2_2") (pintype "passive"))
      (node (ref "X2") (pin "3") (pinfunction "KL_3") (pintype "passive"))
      (node (ref "X2") (pin "5") (pinfunction "KL_5") (pintype "passive"))
      (node (ref "X3") (pin "2") (pinfunction "KL_2") (pintype "passive"))
    )
    (net (code "96") (name "Net-(X3C-KL)") (class "Default")
      (node (ref "D4") (pin "C") (pinfunction "C_C") (pintype "passive"))
      (node (ref "X3") (pin "3") (pinfunction "KL_3") (pintype "passive"))
      (node (ref "X3") (pin "4") (pinfunction "KL_4") (pintype "passive"))
      (node (ref "X3") (pin "5") (pinfunction "KL_5") (pintype "passive"))
    )
    (net (code "97") (name "Net-(X7A-KL)") (class "Default")
      (node (ref "R73") (pin "2") (pinfunction "2_2") (pintype "passive"))
      (node (ref "R74") (pin "1") (pinfunction "1_1") (pintype "passive"))
      (node (ref "X7") (pin "1") (pinfunction "KL_1") (pintype "passive"))
    )
    (net (code "98") (name "Net-(X7B-KL)") (class "Default")
      (node (ref "R75") (pin "S") (pinfunction "S_S") (pintype "passive"))
      (node (ref "X7") (pin "2") (pinfunction "KL_2") (pintype "passive"))
    )
    (net (code "99") (name "Net-(X8B-KL)") (class "Default")
      (node (ref "C11") (pin "1") (pinfunction "1_1") (pintype "passive"))
      (node (ref "R79") (pin "2") (pinfunction "2_2") (pintype "passive"))
      (node (ref "X8") (pin "2") (pinfunction "KL_2") (pintype "passive"))
    )
    (net (code "100") (name "unconnected-(IC1-O3-Pad14)") (class "Default")
      (node (ref "IC1") (pin "14") (pinfunction "O3_14") (pintype "open_collector"))
    )
    (net (code "101") (name "unconnected-(IC2-DIS-Pad7)") (class "Default")
      (node (ref "IC2") (pin "7") (pinfunction "DIS_7") (pintype "input"))
    )
    (net (code "102") (name "unconnected-(IC2-R-Pad4)") (class "Default")
      (node (ref "IC2") (pin "4") (pinfunction "R_4") (pintype "input"))
    )
    (net (code "103") (name "unconnected-(IC2-TR-Pad2)") (class "Default")
      (node (ref "IC2") (pin "2") (pinfunction "TR_2") (pintype "input"))
    )
    (net (code "104") (name "unconnected-(U1-DB0(LSB)-Pad14)") (class "Default")
      (node (ref "U1") (pin "14") (pinfunction "DB0(LSB)_14") (pintype "output"))
    )
    (net (code "105") (name "unconnected-(U1-DB1-Pad13)") (class "Default")
      (node (ref "U1") (pin "13") (pinfunction "DB1_13") (pintype "output"))
    )
  )
)
